# 02-MCU.net
KiCad netlist of a schematic drawn in Altium Designer
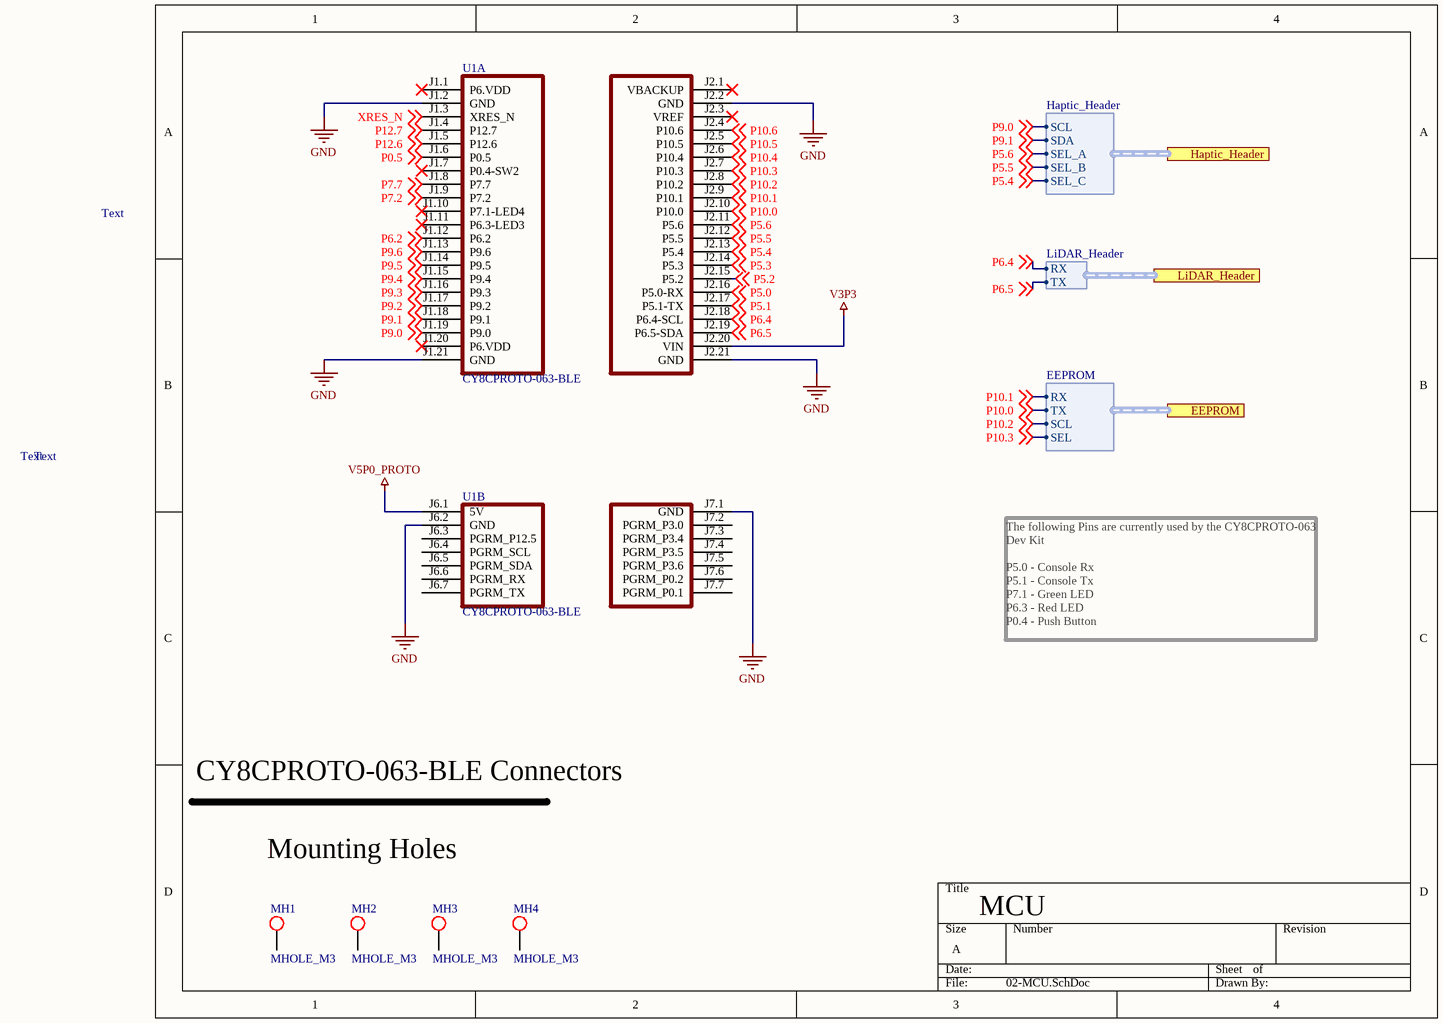
[diagram p0: 02-MCU.SchDoc]

(export (version "E")
  (design (tool "Eeschema 10.0.6"))
  (components
    (comp (ref "MH1")
      (value "MHOLE_M3")
      (footprint "MHOLE_M3")
      (description "Mounting Hole - M3 Metric")
      (libsource (lib "uw-madison-parts") (part "MHOLE_M3"))
    )
    (comp (ref "MH2")
      (value "MHOLE_M3")
      (footprint "MHOLE_M3")
      (description "Mounting Hole - M3 Metric")
      (libsource (lib "uw-madison-parts") (part "MHOLE_M3"))
    )
    (comp (ref "MH3")
      (value "MHOLE_M3")
      (footprint "MHOLE_M3")
      (description "Mounting Hole - M3 Metric")
      (libsource (lib "uw-madison-parts") (part "MHOLE_M3"))
    )
    (comp (ref "MH4")
      (value "MHOLE_M3")
      (footprint "MHOLE_M3")
      (description "Mounting Hole - M3 Metric")
      (libsource (lib "uw-madison-parts") (part "MHOLE_M3"))
    )
    (comp (ref "U1")
      (value "CY8CPROTO-063-BLE")
      (footprint "CY8CPROTO-063-BLE")
      (libsource (lib "ECE453_S24") (part "IC_CY8CPROTO-063-BLE"))
    )
  )
  (nets
    (net (code "7") (name "GND") (class "Default")
      (node (ref "U1") (pin "J1.2") (pinfunction "GND_J1.2") (pintype "passive"))
      (node (ref "U1") (pin "J1.21") (pinfunction "GND_J1.21") (pintype "passive"))
      (node (ref "U1") (pin "J2.2") (pinfunction "GND_J2.2") (pintype "passive"))
      (node (ref "U1") (pin "J2.21") (pinfunction "GND_J2.21") (pintype "passive"))
      (node (ref "U1") (pin "J6.2") (pinfunction "GND_J6.2") (pintype "passive"))
      (node (ref "U1") (pin "J7.1") (pinfunction "GND_J7.1") (pintype "passive"))
    )
    (net (code "8") (name "P0.5") (class "Default")
      (node (ref "U1") (pin "J1.6") (pinfunction "P0.5_J1.6") (pintype "passive"))
    )
    (net (code "9") (name "P5.0") (class "Default")
      (node (ref "U1") (pin "J2.16") (pinfunction "P5.0-RX_J2.16") (pintype "passive"))
    )
    (net (code "10") (name "P5.1") (class "Default")
      (node (ref "U1") (pin "J2.17") (pinfunction "P5.1-TX_J2.17") (pintype "passive"))
    )
    (net (code "11") (name "P5.2") (class "Default")
      (node (ref "U1") (pin "J2.15") (pinfunction "P5.2_J2.15") (pintype "passive"))
    )
    (net (code "12") (name "P5.3") (class "Default")
      (node (ref "U1") (pin "J2.14") (pinfunction "P5.3_J2.14") (pintype "passive"))
    )
    (net (code "13") (name "P5.4") (class "Default")
      (node (ref "U1") (pin "J2.13") (pinfunction "P5.4_J2.13") (pintype "passive"))
    )
    (net (code "14") (name "P5.5") (class "Default")
      (node (ref "U1") (pin "J2.12") (pinfunction "P5.5_J2.12") (pintype "passive"))
    )
    (net (code "15") (name "P5.6") (class "Default")
      (node (ref "U1") (pin "J2.11") (pinfunction "P5.6_J2.11") (pintype "passive"))
    )
    (net (code "16") (name "P6.2") (class "Default")
      (node (ref "U1") (pin "J1.12") (pinfunction "P6.2_J1.12") (pintype "passive"))
    )
    (net (code "17") (name "P6.4") (class "Default")
      (node (ref "U1") (pin "J2.18") (pinfunction "P6.4-SCL_J2.18") (pintype "passive"))
    )
    (net (code "18") (name "P6.5") (class "Default")
      (node (ref "U1") (pin "J2.19") (pinfunction "P6.5-SDA_J2.19") (pintype "passive"))
    )
    (net (code "19") (name "P7.2") (class "Default")
      (node (ref "U1") (pin "J1.9") (pinfunction "P7.2_J1.9") (pintype "passive"))
    )
    (net (code "20") (name "P7.7") (class "Default")
      (node (ref "U1") (pin "J1.8") (pinfunction "P7.7_J1.8") (pintype "passive"))
    )
    (net (code "21") (name "P9.0") (class "Default")
      (node (ref "U1") (pin "J1.19") (pinfunction "P9.0_J1.19") (pintype "passive"))
    )
    (net (code "22") (name "P9.1") (class "Default")
      (node (ref "U1") (pin "J1.18") (pinfunction "P9.1_J1.18") (pintype "passive"))
    )
    (net (code "23") (name "P9.2") (class "Default")
      (node (ref "U1") (pin "J1.17") (pinfunction "P9.2_J1.17") (pintype "passive"))
    )
    (net (code "24") (name "P9.3") (class "Default")
      (node (ref "U1") (pin "J1.16") (pinfunction "P9.3_J1.16") (pintype "passive"))
    )
    (net (code "25") (name "P9.4") (class "Default")
      (node (ref "U1") (pin "J1.15") (pinfunction "P9.4_J1.15") (pintype "passive"))
    )
    (net (code "26") (name "P9.5") (class "Default")
      (node (ref "U1") (pin "J1.14") (pinfunction "P9.5_J1.14") (pintype "passive"))
    )
    (net (code "27") (name "P9.6") (class "Default")
      (node (ref "U1") (pin "J1.13") (pinfunction "P9.6_J1.13") (pintype "passive"))
    )
    (net (code "28") (name "P10.0") (class "Default")
      (node (ref "U1") (pin "J2.10") (pinfunction "P10.0_J2.10") (pintype "passive"))
    )
    (net (code "29") (name "P10.1") (class "Default")
      (node (ref "U1") (pin "J2.9") (pinfunction "P10.1_J2.9") (pintype "passive"))
    )
    (net (code "30") (name "P10.2") (class "Default")
      (node (ref "U1") (pin "J2.8") (pinfunction "P10.2_J2.8") (pintype "passive"))
    )
    (net (code "31") (name "P10.3") (class "Default")
      (node (ref "U1") (pin "J2.7") (pinfunction "P10.3_J2.7") (pintype "passive"))
    )
    (net (code "32") (name "P10.4") (class "Default")
      (node (ref "U1") (pin "J2.6") (pinfunction "P10.4_J2.6") (pintype "passive"))
    )
    (net (code "33") (name "P10.5") (class "Default")
      (node (ref "U1") (pin "J2.5") (pinfunction "P10.5_J2.5") (pintype "passive"))
    )
    (net (code "34") (name "P10.6") (class "Default")
      (node (ref "U1") (pin "J2.4") (pinfunction "P10.6_J2.4") (pintype "passive"))
    )
    (net (code "35") (name "P12.6") (class "Default")
      (node (ref "U1") (pin "J1.5") (pinfunction "P12.6_J1.5") (pintype "passive"))
    )
    (net (code "36") (name "P12.7") (class "Default")
      (node (ref "U1") (pin "J1.4") (pinfunction "P12.7_J1.4") (pintype "passive"))
    )
    (net (code "37") (name "V3P3") (class "Default")
      (node (ref "U1") (pin "J2.20") (pinfunction "VIN_J2.20") (pintype "passive"))
    )
    (net (code "38") (name "V5P0_PROTO") (class "Default")
      (node (ref "U1") (pin "J6.1") (pinfunction "5V_J6.1") (pintype "passive"))
    )
    (net (code "39") (name "XRES_N") (class "Default")
      (node (ref "U1") (pin "J1.3") (pinfunction "XRES_N_J1.3") (pintype "passive"))
    )
    (net (code "40") (name "unconnected-(MH1-Pad1)") (class "Default")
      (node (ref "MH1") (pin "1") (pintype "passive"))
    )
    (net (code "41") (name "unconnected-(MH2-Pad1)") (class "Default")
      (node (ref "MH2") (pin "1") (pintype "passive"))
    )
    (net (code "42") (name "unconnected-(MH3-Pad1)") (class "Default")
      (node (ref "MH3") (pin "1") (pintype "passive"))
    )
    (net (code "43") (name "unconnected-(MH4-Pad1)") (class "Default")
      (node (ref "MH4") (pin "1") (pintype "passive"))
    )
    (net (code "44") (name "unconnected-(U1A-P0.4-SW2-PadJ1.7)") (class "Default")
      (node (ref "U1") (pin "J1.7") (pinfunction "P0.4-SW2_J1.7") (pintype "passive+no_connect"))
    )
    (net (code "45") (name "unconnected-(U1A-P6.3-LED3-PadJ1.11)") (class "Default")
      (node (ref "U1") (pin "J1.11") (pinfunction "P6.3-LED3_J1.11") (pintype "passive+no_connect"))
    )
    (net (code "46") (name "unconnected-(U1A-P6.VDD-PadJ1.1)") (class "Default")
      (node (ref "U1") (pin "J1.1") (pinfunction "P6.VDD_J1.1") (pintype "passive+no_connect"))
    )
    (net (code "47") (name "unconnected-(U1A-P6.VDD-PadJ1.20)") (class "Default")
      (node (ref "U1") (pin "J1.20") (pinfunction "P6.VDD_J1.20") (pintype "passive+no_connect"))
    )
    (net (code "48") (name "unconnected-(U1A-P7.1-LED4-PadJ1.10)") (class "Default")
      (node (ref "U1") (pin "J1.10") (pinfunction "P7.1-LED4_J1.10") (pintype "passive+no_connect"))
    )
    (net (code "49") (name "unconnected-(U1A-VBACKUP-PadJ2.1)") (class "Default")
      (node (ref "U1") (pin "J2.1") (pinfunction "VBACKUP_J2.1") (pintype "passive+no_connect"))
    )
    (net (code "50") (name "unconnected-(U1A-VREF-PadJ2.3)") (class "Default")
      (node (ref "U1") (pin "J2.3") (pinfunction "VREF_J2.3") (pintype "passive+no_connect"))
    )
    (net (code "51") (name "unconnected-(U1B-PGRM_P0.1-PadJ7.7)") (class "Default")
      (node (ref "U1") (pin "J7.7") (pinfunction "PGRM_P0.1_J7.7") (pintype "passive"))
    )
    (net (code "52") (name "unconnected-(U1B-PGRM_P0.2-PadJ7.6)") (class "Default")
      (node (ref "U1") (pin "J7.6") (pinfunction "PGRM_P0.2_J7.6") (pintype "passive"))
    )
    (net (code "53") (name "unconnected-(U1B-PGRM_P3.0-PadJ7.2)") (class "Default")
      (node (ref "U1") (pin "J7.2") (pinfunction "PGRM_P3.0_J7.2") (pintype "passive"))
    )
    (net (code "54") (name "unconnected-(U1B-PGRM_P3.4-PadJ7.3)") (class "Default")
      (node (ref "U1") (pin "J7.3") (pinfunction "PGRM_P3.4_J7.3") (pintype "passive"))
    )
    (net (code "55") (name "unconnected-(U1B-PGRM_P3.5-PadJ7.4)") (class "Default")
      (node (ref "U1") (pin "J7.4") (pinfunction "PGRM_P3.5_J7.4") (pintype "passive"))
    )
    (net (code "56") (name "unconnected-(U1B-PGRM_P3.6-PadJ7.5)") (class "Default")
      (node (ref "U1") (pin "J7.5") (pinfunction "PGRM_P3.6_J7.5") (pintype "passive"))
    )
    (net (code "57") (name "unconnected-(U1B-PGRM_P12.5-PadJ6.3)") (class "Default")
      (node (ref "U1") (pin "J6.3") (pinfunction "PGRM_P12.5_J6.3") (pintype "passive"))
    )
    (net (code "58") (name "unconnected-(U1B-PGRM_RX-PadJ6.6)") (class "Default")
      (node (ref "U1") (pin "J6.6") (pinfunction "PGRM_RX_J6.6") (pintype "passive"))
    )
    (net (code "59") (name "unconnected-(U1B-PGRM_SCL-PadJ6.4)") (class "Default")
      (node (ref "U1") (pin "J6.4") (pinfunction "PGRM_SCL_J6.4") (pintype "passive"))
    )
    (net (code "60") (name "unconnected-(U1B-PGRM_SDA-PadJ6.5)") (class "Default")
      (node (ref "U1") (pin "J6.5") (pinfunction "PGRM_SDA_J6.5") (pintype "passive"))
    )
    (net (code "61") (name "unconnected-(U1B-PGRM_TX-PadJ6.7)") (class "Default")
      (node (ref "U1") (pin "J6.7") (pinfunction "PGRM_TX_J6.7") (pintype "passive"))
    )
  )
)
